# pico_v2.net
KiCad netlist of a schematic drawn in EAGLE
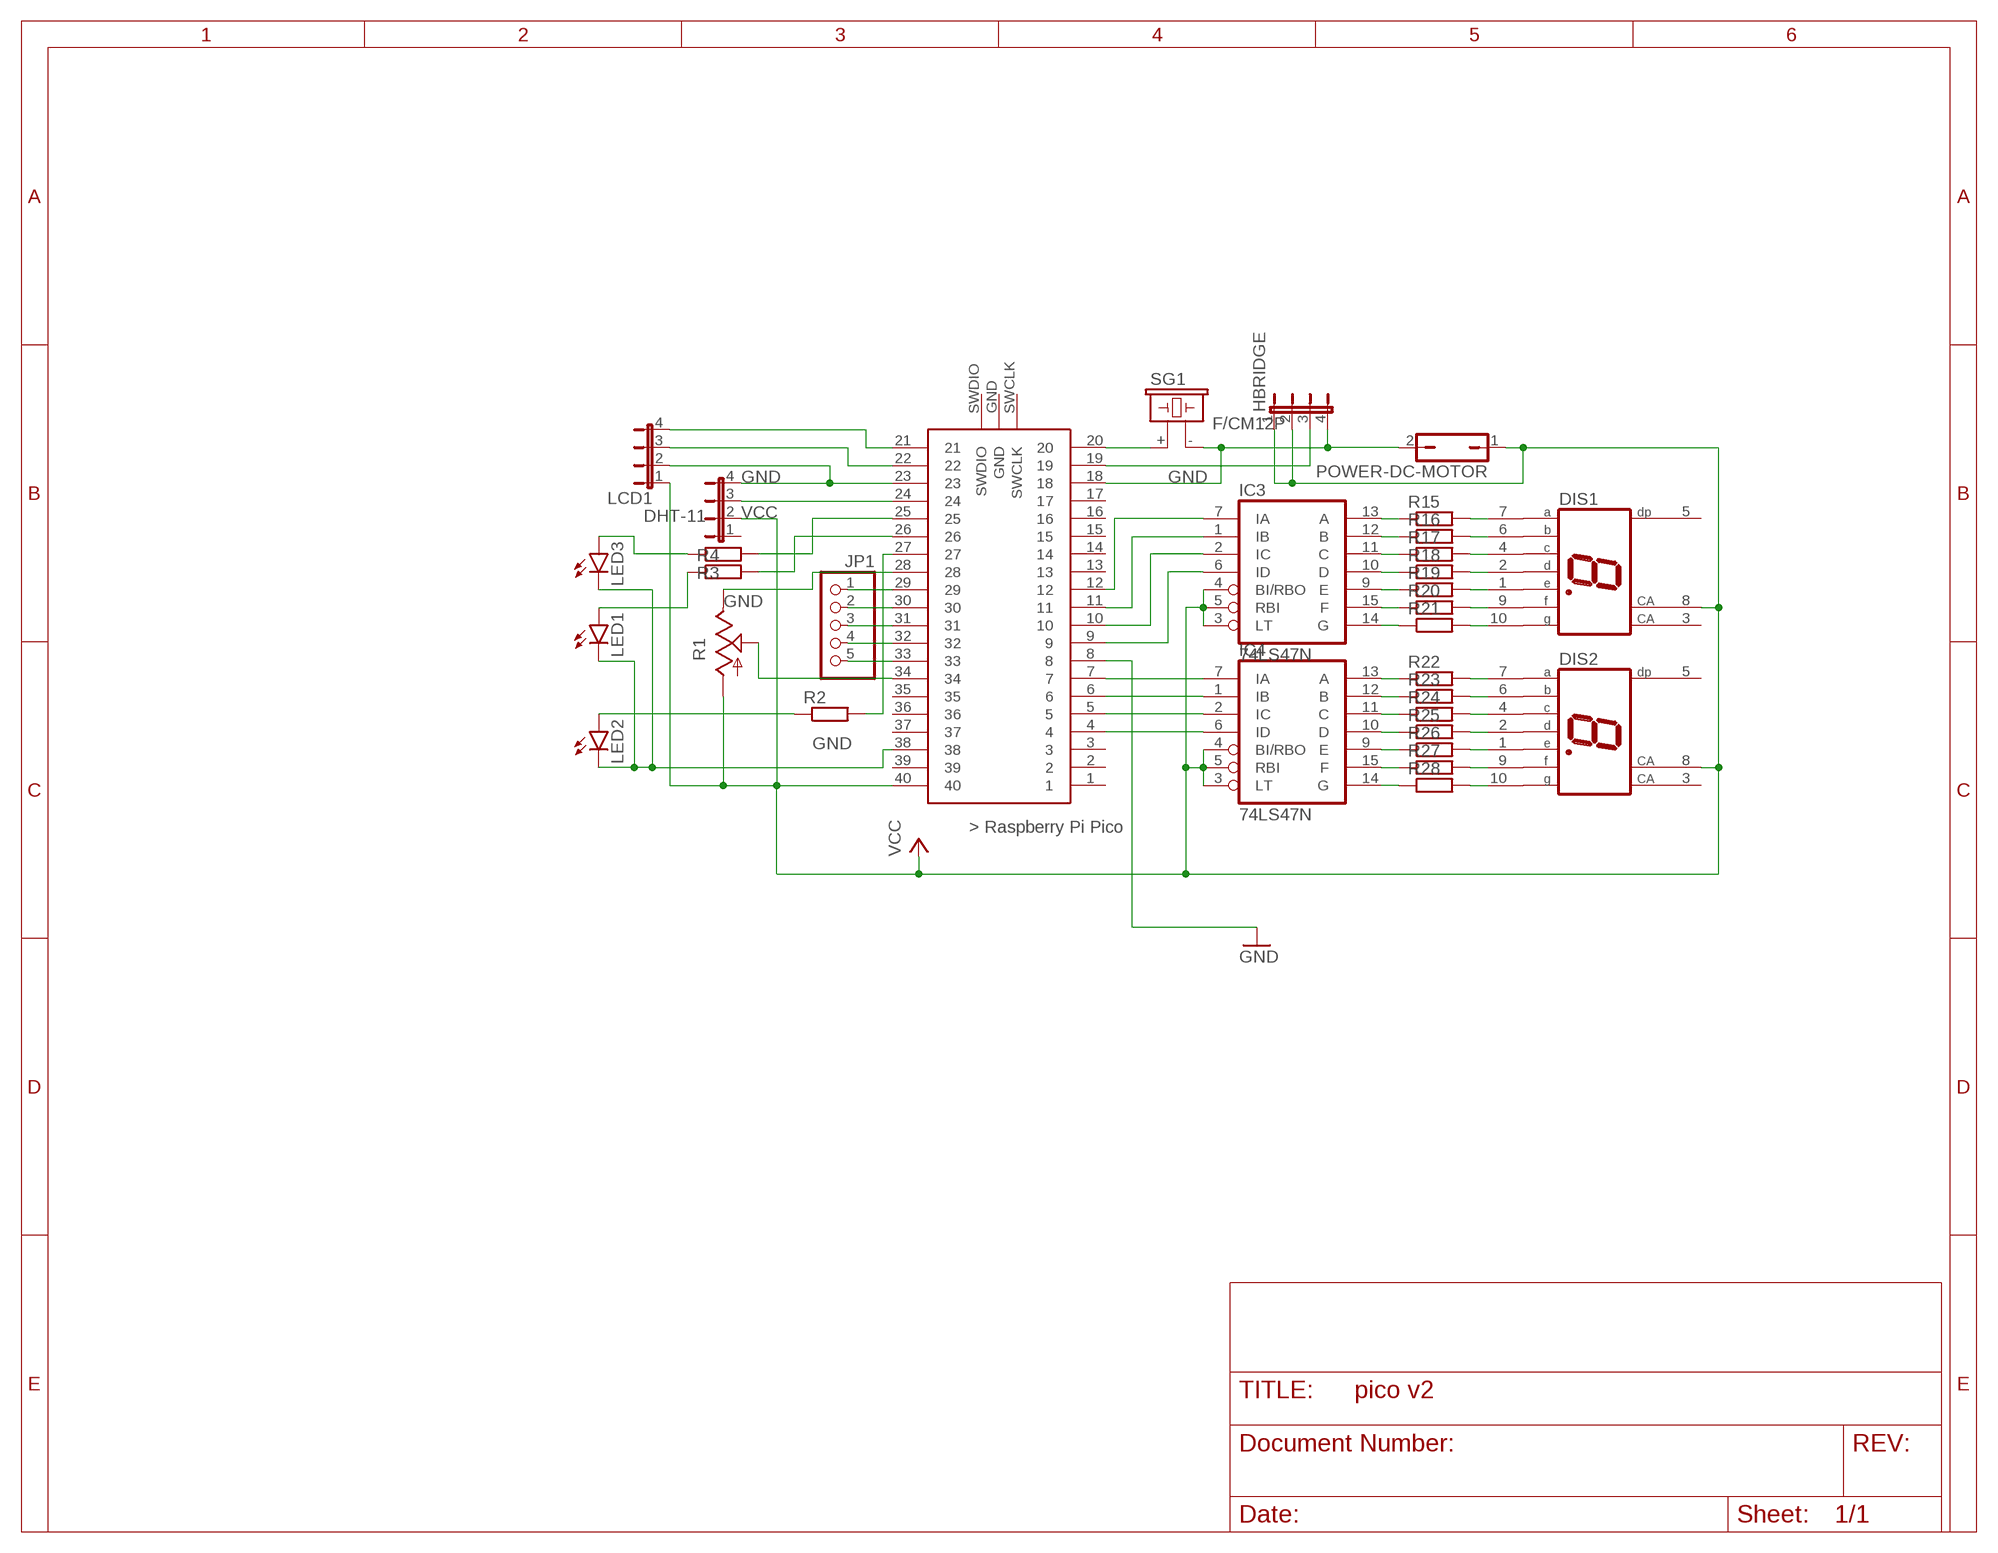
[diagram p0: schematic, sheet 1]

(export (version "E")
  (design (tool "Eeschema 10.0.6"))
  (components
    (comp (ref "DHT-11")
      (value "JP4E")
      (footprint "eagle-import:JP4")
      (libsource (lib "eagle-import") (part "JP4E"))
    )
    (comp (ref "DIS1")
      (value "HD-H101")
      (footprint "eagle-import:HDSP-M")
      (libsource (lib "eagle-import") (part "HD-H101"))
    )
    (comp (ref "DIS2")
      (value "HD-H101")
      (footprint "eagle-import:HDSP-M")
      (libsource (lib "eagle-import") (part "HD-H101"))
    )
    (comp (ref "HBRIDGE")
      (value "JP4E")
      (footprint "eagle-import:JP4")
      (libsource (lib "eagle-import") (part "JP4E"))
    )
    (comp (ref "IC3")
      (value "74LS47N")
      (footprint "eagle-import:DIL16")
      (libsource (lib "eagle-import") (part "7447NLS"))
    )
    (comp (ref "IC4")
      (value "74LS47N")
      (footprint "eagle-import:DIL16")
      (libsource (lib "eagle-import") (part "7447NLS"))
    )
    (comp (ref "JP1")
      (value "PINHD-1X5")
      (footprint "eagle-import:1X05")
      (libsource (lib "eagle-import") (part "PINHD-1X5"))
    )
    (comp (ref "LCD1")
      (value "JP4E")
      (footprint "eagle-import:JP4")
      (libsource (lib "eagle-import") (part "JP4E"))
    )
    (comp (ref "LED1")
      (value "LED5MM")
      (footprint "eagle-import:LED5MM")
      (libsource (lib "eagle-import") (part "LED5MM"))
    )
    (comp (ref "LED2")
      (value "LED5MM")
      (footprint "eagle-import:LED5MM")
      (libsource (lib "eagle-import") (part "LED5MM"))
    )
    (comp (ref "LED3")
      (value "LED5MM")
      (footprint "eagle-import:LED5MM")
      (libsource (lib "eagle-import") (part "LED5MM"))
    )
    (comp (ref "POWER-DC-MOTOR")
      (value "JP1Q")
      (footprint "eagle-import:JP1")
      (libsource (lib "eagle-import") (part "JP1Q"))
    )
    (comp (ref "R1")
      (value "TRIM_US-CA6V")
      (footprint "eagle-import:CA6V")
      (libsource (lib "eagle-import") (part "TRIM_US-CA6V"))
    )
    (comp (ref "R2")
      (value "R-EU_0207/10")
      (footprint "eagle-import:0207_10")
      (libsource (lib "eagle-import") (part "R-EU_0207/10"))
    )
    (comp (ref "R3")
      (value "R-EU_0207/10")
      (footprint "eagle-import:0207_10")
      (libsource (lib "eagle-import") (part "R-EU_0207/10"))
    )
    (comp (ref "R4")
      (value "R-EU_0207/10")
      (footprint "eagle-import:0207_10")
      (libsource (lib "eagle-import") (part "R-EU_0207/10"))
    )
    (comp (ref "R15")
      (value "R-EU_0207/12")
      (footprint "eagle-import:0207_12")
      (libsource (lib "eagle-import") (part "R-EU_0207/12"))
    )
    (comp (ref "R16")
      (value "R-EU_0207/12")
      (footprint "eagle-import:0207_12")
      (libsource (lib "eagle-import") (part "R-EU_0207/12"))
    )
    (comp (ref "R17")
      (value "R-EU_0207/12")
      (footprint "eagle-import:0207_12")
      (libsource (lib "eagle-import") (part "R-EU_0207/12"))
    )
    (comp (ref "R18")
      (value "R-EU_0207/12")
      (footprint "eagle-import:0207_12")
      (libsource (lib "eagle-import") (part "R-EU_0207/12"))
    )
    (comp (ref "R19")
      (value "R-EU_0207/12")
      (footprint "eagle-import:0207_12")
      (libsource (lib "eagle-import") (part "R-EU_0207/12"))
    )
    (comp (ref "R20")
      (value "R-EU_0207/12")
      (footprint "eagle-import:0207_12")
      (libsource (lib "eagle-import") (part "R-EU_0207/12"))
    )
    (comp (ref "R21")
      (value "R-EU_0207/12")
      (footprint "eagle-import:0207_12")
      (libsource (lib "eagle-import") (part "R-EU_0207/12"))
    )
    (comp (ref "R22")
      (value "R-EU_0207/12")
      (footprint "eagle-import:0207_12")
      (libsource (lib "eagle-import") (part "R-EU_0207/12"))
    )
    (comp (ref "R23")
      (value "R-EU_0207/12")
      (footprint "eagle-import:0207_12")
      (libsource (lib "eagle-import") (part "R-EU_0207/12"))
    )
    (comp (ref "R24")
      (value "R-EU_0207/12")
      (footprint "eagle-import:0207_12")
      (libsource (lib "eagle-import") (part "R-EU_0207/12"))
    )
    (comp (ref "R25")
      (value "R-EU_0207/12")
      (footprint "eagle-import:0207_12")
      (libsource (lib "eagle-import") (part "R-EU_0207/12"))
    )
    (comp (ref "R26")
      (value "R-EU_0207/12")
      (footprint "eagle-import:0207_12")
      (libsource (lib "eagle-import") (part "R-EU_0207/12"))
    )
    (comp (ref "R27")
      (value "R-EU_0207/12")
      (footprint "eagle-import:0207_12")
      (libsource (lib "eagle-import") (part "R-EU_0207/12"))
    )
    (comp (ref "R28")
      (value "R-EU_0207/12")
      (footprint "eagle-import:0207_12")
      (libsource (lib "eagle-import") (part "R-EU_0207/12"))
    )
    (comp (ref "SG1")
      (value "F/CM12P")
      (footprint "eagle-import:F_CM12P")
      (libsource (lib "eagle-import") (part "F/CM12P"))
    )
    (comp (ref "U$1")
      (value "RASPBERRY-PI-PICO_TH")
      (footprint "eagle-import:FT_RASPBERRY-PI-PICO_TH")
      (libsource (lib "eagle-import") (part "RASPBERRY-PI-PICO_TH"))
    )
  )
  (nets
    (net (code "1") (name "GND") (class "Default")
      (node (ref "DHT-11") (pin "4") (pinfunction "4_4") (pintype "passive"))
      (node (ref "HBRIDGE") (pin "4") (pinfunction "4_4") (pintype "passive"))
      (node (ref "LCD1") (pin "2") (pinfunction "2_2") (pintype "passive"))
      (node (ref "LED1") (pin "K") (pinfunction "C_K") (pintype "passive"))
      (node (ref "LED2") (pin "K") (pinfunction "C_K") (pintype "passive"))
      (node (ref "LED3") (pin "K") (pinfunction "C_K") (pintype "passive"))
      (node (ref "POWER-DC-MOTOR") (pin "2") (pinfunction "2_2") (pintype "passive"))
      (node (ref "R1") (pin "E") (pinfunction "E_E") (pintype "passive"))
      (node (ref "SG1") (pin "-") (pinfunction "2_-") (pintype "passive"))
      (node (ref "U$1") (pin "18") (pinfunction "18_18") (pintype "bidirectional"))
      (node (ref "U$1") (pin "23") (pinfunction "23_23") (pintype "bidirectional"))
      (node (ref "U$1") (pin "28") (pinfunction "28_28") (pintype "bidirectional"))
      (node (ref "U$1") (pin "38") (pinfunction "38_38") (pintype "bidirectional"))
      (node (ref "U$1") (pin "8") (pinfunction "8_8") (pintype "bidirectional"))
    )
    (net (code "2") (name "Net-(DHT-11-Pad3)") (class "Default")
      (node (ref "DHT-11") (pin "3") (pinfunction "3_3") (pintype "passive"))
      (node (ref "U$1") (pin "24") (pinfunction "24_24") (pintype "bidirectional"))
    )
    (net (code "3") (name "Net-(DIS1-A)") (class "Default")
      (node (ref "DIS1") (pin "7") (pinfunction "A_7") (pintype "passive"))
      (node (ref "R15") (pin "2") (pinfunction "2_2") (pintype "passive"))
    )
    (net (code "4") (name "Net-(DIS1-B)") (class "Default")
      (node (ref "DIS1") (pin "6") (pinfunction "B_6") (pintype "passive"))
      (node (ref "R16") (pin "2") (pinfunction "2_2") (pintype "passive"))
    )
    (net (code "5") (name "Net-(DIS1-C)") (class "Default")
      (node (ref "DIS1") (pin "4") (pinfunction "C_4") (pintype "passive"))
      (node (ref "R17") (pin "2") (pinfunction "2_2") (pintype "passive"))
    )
    (net (code "6") (name "Net-(DIS1-D)") (class "Default")
      (node (ref "DIS1") (pin "2") (pinfunction "D_2") (pintype "passive"))
      (node (ref "R18") (pin "2") (pinfunction "2_2") (pintype "passive"))
    )
    (net (code "7") (name "Net-(DIS1-E)") (class "Default")
      (node (ref "DIS1") (pin "1") (pinfunction "E_1") (pintype "passive"))
      (node (ref "R19") (pin "2") (pinfunction "2_2") (pintype "passive"))
    )
    (net (code "8") (name "Net-(DIS1-F)") (class "Default")
      (node (ref "DIS1") (pin "9") (pinfunction "F_9") (pintype "passive"))
      (node (ref "R20") (pin "2") (pinfunction "2_2") (pintype "passive"))
    )
    (net (code "9") (name "Net-(DIS1-G)") (class "Default")
      (node (ref "DIS1") (pin "10") (pinfunction "G_10") (pintype "passive"))
      (node (ref "R21") (pin "2") (pinfunction "2_2") (pintype "passive"))
    )
    (net (code "10") (name "Net-(DIS2-A)") (class "Default")
      (node (ref "DIS2") (pin "7") (pinfunction "A_7") (pintype "passive"))
      (node (ref "R22") (pin "2") (pinfunction "2_2") (pintype "passive"))
    )
    (net (code "11") (name "Net-(DIS2-B)") (class "Default")
      (node (ref "DIS2") (pin "6") (pinfunction "B_6") (pintype "passive"))
      (node (ref "R23") (pin "2") (pinfunction "2_2") (pintype "passive"))
    )
    (net (code "12") (name "Net-(DIS2-C)") (class "Default")
      (node (ref "DIS2") (pin "4") (pinfunction "C_4") (pintype "passive"))
      (node (ref "R24") (pin "2") (pinfunction "2_2") (pintype "passive"))
    )
    (net (code "13") (name "Net-(DIS2-D)") (class "Default")
      (node (ref "DIS2") (pin "2") (pinfunction "D_2") (pintype "passive"))
      (node (ref "R25") (pin "2") (pinfunction "2_2") (pintype "passive"))
    )
    (net (code "14") (name "Net-(DIS2-E)") (class "Default")
      (node (ref "DIS2") (pin "1") (pinfunction "E_1") (pintype "passive"))
      (node (ref "R26") (pin "2") (pinfunction "2_2") (pintype "passive"))
    )
    (net (code "15") (name "Net-(DIS2-F)") (class "Default")
      (node (ref "DIS2") (pin "9") (pinfunction "F_9") (pintype "passive"))
      (node (ref "R27") (pin "2") (pinfunction "2_2") (pintype "passive"))
    )
    (net (code "16") (name "Net-(DIS2-G)") (class "Default")
      (node (ref "DIS2") (pin "10") (pinfunction "G_10") (pintype "passive"))
      (node (ref "R28") (pin "2") (pinfunction "2_2") (pintype "passive"))
    )
    (net (code "17") (name "Net-(HBRIDGE-Pad3)") (class "Default")
      (node (ref "HBRIDGE") (pin "3") (pinfunction "3_3") (pintype "passive"))
      (node (ref "U$1") (pin "19") (pinfunction "19_19") (pintype "bidirectional"))
    )
    (net (code "18") (name "Net-(IC3A-A)") (class "Default")
      (node (ref "IC3") (pin "13") (pinfunction "A_13") (pintype "output"))
      (node (ref "R15") (pin "1") (pinfunction "1_1") (pintype "passive"))
    )
    (net (code "19") (name "Net-(IC3A-B)") (class "Default")
      (node (ref "IC3") (pin "12") (pinfunction "B_12") (pintype "output"))
      (node (ref "R16") (pin "1") (pinfunction "1_1") (pintype "passive"))
    )
    (net (code "20") (name "Net-(IC3A-C)") (class "Default")
      (node (ref "IC3") (pin "11") (pinfunction "C_11") (pintype "output"))
      (node (ref "R17") (pin "1") (pinfunction "1_1") (pintype "passive"))
    )
    (net (code "21") (name "Net-(IC3A-D)") (class "Default")
      (node (ref "IC3") (pin "10") (pinfunction "D_10") (pintype "output"))
      (node (ref "R18") (pin "1") (pinfunction "1_1") (pintype "passive"))
    )
    (net (code "22") (name "Net-(IC3A-E)") (class "Default")
      (node (ref "IC3") (pin "9") (pinfunction "E_9") (pintype "output"))
      (node (ref "R19") (pin "1") (pinfunction "1_1") (pintype "passive"))
    )
    (net (code "23") (name "Net-(IC3A-F)") (class "Default")
      (node (ref "IC3") (pin "15") (pinfunction "F_15") (pintype "output"))
      (node (ref "R20") (pin "1") (pinfunction "1_1") (pintype "passive"))
    )
    (net (code "24") (name "Net-(IC3A-G)") (class "Default")
      (node (ref "IC3") (pin "14") (pinfunction "G_14") (pintype "output"))
      (node (ref "R21") (pin "1") (pinfunction "1_1") (pintype "passive"))
    )
    (net (code "25") (name "Net-(IC3A-IA)") (class "Default")
      (node (ref "IC3") (pin "7") (pinfunction "IA_7") (pintype "input"))
      (node (ref "U$1") (pin "12") (pinfunction "12_12") (pintype "bidirectional"))
    )
    (net (code "26") (name "Net-(IC3A-IB)") (class "Default")
      (node (ref "IC3") (pin "1") (pinfunction "IB_1") (pintype "input"))
      (node (ref "U$1") (pin "11") (pinfunction "11_11") (pintype "bidirectional"))
    )
    (net (code "27") (name "Net-(IC3A-IC)") (class "Default")
      (node (ref "IC3") (pin "2") (pinfunction "IC_2") (pintype "input"))
      (node (ref "U$1") (pin "10") (pinfunction "10_10") (pintype "bidirectional"))
    )
    (net (code "28") (name "Net-(IC3A-ID)") (class "Default")
      (node (ref "IC3") (pin "6") (pinfunction "ID_6") (pintype "input"))
      (node (ref "U$1") (pin "9") (pinfunction "9_9") (pintype "bidirectional"))
    )
    (net (code "29") (name "Net-(IC4A-A)") (class "Default")
      (node (ref "IC4") (pin "13") (pinfunction "A_13") (pintype "output"))
      (node (ref "R22") (pin "1") (pinfunction "1_1") (pintype "passive"))
    )
    (net (code "30") (name "Net-(IC4A-B)") (class "Default")
      (node (ref "IC4") (pin "12") (pinfunction "B_12") (pintype "output"))
      (node (ref "R23") (pin "1") (pinfunction "1_1") (pintype "passive"))
    )
    (net (code "31") (name "Net-(IC4A-C)") (class "Default")
      (node (ref "IC4") (pin "11") (pinfunction "C_11") (pintype "output"))
      (node (ref "R24") (pin "1") (pinfunction "1_1") (pintype "passive"))
    )
    (net (code "32") (name "Net-(IC4A-D)") (class "Default")
      (node (ref "IC4") (pin "10") (pinfunction "D_10") (pintype "output"))
      (node (ref "R25") (pin "1") (pinfunction "1_1") (pintype "passive"))
    )
    (net (code "33") (name "Net-(IC4A-E)") (class "Default")
      (node (ref "IC4") (pin "9") (pinfunction "E_9") (pintype "output"))
      (node (ref "R26") (pin "1") (pinfunction "1_1") (pintype "passive"))
    )
    (net (code "34") (name "Net-(IC4A-F)") (class "Default")
      (node (ref "IC4") (pin "15") (pinfunction "F_15") (pintype "output"))
      (node (ref "R27") (pin "1") (pinfunction "1_1") (pintype "passive"))
    )
    (net (code "35") (name "Net-(IC4A-G)") (class "Default")
      (node (ref "IC4") (pin "14") (pinfunction "G_14") (pintype "output"))
      (node (ref "R28") (pin "1") (pinfunction "1_1") (pintype "passive"))
    )
    (net (code "36") (name "Net-(IC4A-IA)") (class "Default")
      (node (ref "IC4") (pin "7") (pinfunction "IA_7") (pintype "input"))
      (node (ref "U$1") (pin "7") (pinfunction "7_7") (pintype "bidirectional"))
    )
    (net (code "37") (name "Net-(IC4A-IB)") (class "Default")
      (node (ref "IC4") (pin "1") (pinfunction "IB_1") (pintype "input"))
      (node (ref "U$1") (pin "6") (pinfunction "6_6") (pintype "bidirectional"))
    )
    (net (code "38") (name "Net-(IC4A-IC)") (class "Default")
      (node (ref "IC4") (pin "2") (pinfunction "IC_2") (pintype "input"))
      (node (ref "U$1") (pin "5") (pinfunction "5_5") (pintype "bidirectional"))
    )
    (net (code "39") (name "Net-(IC4A-ID)") (class "Default")
      (node (ref "IC4") (pin "6") (pinfunction "ID_6") (pintype "input"))
      (node (ref "U$1") (pin "4") (pinfunction "4_4") (pintype "bidirectional"))
    )
    (net (code "40") (name "Net-(JP1-Pad1)") (class "Default")
      (node (ref "JP1") (pin "1") (pinfunction "1_1") (pintype "passive"))
      (node (ref "U$1") (pin "29") (pinfunction "29_29") (pintype "bidirectional"))
    )
    (net (code "41") (name "Net-(JP1-Pad2)") (class "Default")
      (node (ref "JP1") (pin "2") (pinfunction "2_2") (pintype "passive"))
      (node (ref "U$1") (pin "30") (pinfunction "30_30") (pintype "bidirectional"))
    )
    (net (code "42") (name "Net-(JP1-Pad3)") (class "Default")
      (node (ref "JP1") (pin "3") (pinfunction "3_3") (pintype "passive"))
      (node (ref "U$1") (pin "31") (pinfunction "31_31") (pintype "bidirectional"))
    )
    (net (code "43") (name "Net-(JP1-Pad4)") (class "Default")
      (node (ref "JP1") (pin "4") (pinfunction "4_4") (pintype "passive"))
      (node (ref "U$1") (pin "32") (pinfunction "32_32") (pintype "bidirectional"))
    )
    (net (code "44") (name "Net-(JP1-Pad5)") (class "Default")
      (node (ref "JP1") (pin "5") (pinfunction "5_5") (pintype "passive"))
      (node (ref "U$1") (pin "33") (pinfunction "33_33") (pintype "bidirectional"))
    )
    (net (code "45") (name "Net-(LCD1-Pad3)") (class "Default")
      (node (ref "LCD1") (pin "3") (pinfunction "3_3") (pintype "passive"))
      (node (ref "U$1") (pin "22") (pinfunction "22_22") (pintype "bidirectional"))
    )
    (net (code "46") (name "Net-(LCD1-Pad4)") (class "Default")
      (node (ref "LCD1") (pin "4") (pinfunction "4_4") (pintype "passive"))
      (node (ref "U$1") (pin "21") (pinfunction "21_21") (pintype "bidirectional"))
    )
    (net (code "47") (name "Net-(LED1-PadA)") (class "Default")
      (node (ref "LED1") (pin "A") (pinfunction "A_A") (pintype "passive"))
      (node (ref "R3") (pin "1") (pinfunction "1_1") (pintype "passive"))
    )
    (net (code "48") (name "Net-(LED2-PadA)") (class "Default")
      (node (ref "LED2") (pin "A") (pinfunction "A_A") (pintype "passive"))
      (node (ref "R2") (pin "1") (pinfunction "1_1") (pintype "passive"))
    )
    (net (code "49") (name "Net-(LED3-PadA)") (class "Default")
      (node (ref "LED3") (pin "A") (pinfunction "A_A") (pintype "passive"))
      (node (ref "R4") (pin "1") (pinfunction "1_1") (pintype "passive"))
    )
    (net (code "50") (name "Net-(R1-PadS)") (class "Default")
      (node (ref "R1") (pin "S") (pinfunction "S_S") (pintype "passive"))
      (node (ref "U$1") (pin "34") (pinfunction "34_34") (pintype "bidirectional"))
    )
    (net (code "51") (name "Net-(R2-Pad2)") (class "Default")
      (node (ref "R2") (pin "2") (pinfunction "2_2") (pintype "passive"))
      (node (ref "U$1") (pin "27") (pinfunction "27_27") (pintype "bidirectional"))
    )
    (net (code "52") (name "Net-(R3-Pad2)") (class "Default")
      (node (ref "R3") (pin "2") (pinfunction "2_2") (pintype "passive"))
      (node (ref "U$1") (pin "26") (pinfunction "26_26") (pintype "bidirectional"))
    )
    (net (code "53") (name "Net-(R4-Pad2)") (class "Default")
      (node (ref "R4") (pin "2") (pinfunction "2_2") (pintype "passive"))
      (node (ref "U$1") (pin "25") (pinfunction "25_25") (pintype "bidirectional"))
    )
    (net (code "54") (name "Net-(SG1-1)") (class "Default")
      (node (ref "SG1") (pin "+") (pinfunction "1_+") (pintype "passive"))
      (node (ref "U$1") (pin "20") (pinfunction "20_20") (pintype "bidirectional"))
    )
    (net (code "55") (name "VCC") (class "Default")
      (node (ref "DHT-11") (pin "2") (pinfunction "2_2") (pintype "passive"))
      (node (ref "DIS1") (pin "8") (pinfunction "CA_8") (pintype "passive"))
      (node (ref "DIS2") (pin "8") (pinfunction "CA_8") (pintype "passive"))
      (node (ref "HBRIDGE") (pin "1") (pinfunction "1_1") (pintype "passive"))
      (node (ref "HBRIDGE") (pin "2") (pinfunction "2_2") (pintype "passive"))
      (node (ref "IC3") (pin "3") (pinfunction "LT_3") (pintype "input"))
      (node (ref "IC3") (pin "4") (pinfunction "BI/RBO_4") (pintype "input"))
      (node (ref "IC3") (pin "5") (pinfunction "RBI_5") (pintype "input"))
      (node (ref "IC4") (pin "3") (pinfunction "LT_3") (pintype "input"))
      (node (ref "IC4") (pin "4") (pinfunction "BI/RBO_4") (pintype "input"))
      (node (ref "IC4") (pin "5") (pinfunction "RBI_5") (pintype "input"))
      (node (ref "LCD1") (pin "1") (pinfunction "1_1") (pintype "passive"))
      (node (ref "POWER-DC-MOTOR") (pin "1") (pinfunction "1_1") (pintype "passive"))
      (node (ref "R1") (pin "A") (pinfunction "A_A") (pintype "passive"))
      (node (ref "U$1") (pin "40") (pinfunction "40_40") (pintype "bidirectional"))
    )
    (net (code "56") (name "unconnected-(DHT-11-Pad1)") (class "Default")
      (node (ref "DHT-11") (pin "1") (pinfunction "1_1") (pintype "passive"))
    )
    (net (code "57") (name "unconnected-(DIS1-CA-Pad3)") (class "Default")
      (node (ref "DIS1") (pin "3") (pinfunction "CA_3") (pintype "passive"))
    )
    (net (code "58") (name "unconnected-(DIS1-DP-Pad5)") (class "Default")
      (node (ref "DIS1") (pin "5") (pinfunction "DP_5") (pintype "passive"))
    )
    (net (code "59") (name "unconnected-(DIS2-CA-Pad3)") (class "Default")
      (node (ref "DIS2") (pin "3") (pinfunction "CA_3") (pintype "passive"))
    )
    (net (code "60") (name "unconnected-(DIS2-DP-Pad5)") (class "Default")
      (node (ref "DIS2") (pin "5") (pinfunction "DP_5") (pintype "passive"))
    )
    (net (code "61") (name "unconnected-(U$1-Pad1)") (class "Default")
      (node (ref "U$1") (pin "1") (pinfunction "1_1") (pintype "bidirectional"))
    )
    (net (code "62") (name "unconnected-(U$1-Pad2)") (class "Default")
      (node (ref "U$1") (pin "2") (pinfunction "2_2") (pintype "bidirectional"))
    )
    (net (code "63") (name "unconnected-(U$1-Pad3)") (class "Default")
      (node (ref "U$1") (pin "3") (pinfunction "3_3") (pintype "bidirectional"))
    )
    (net (code "64") (name "unconnected-(U$1-Pad13)") (class "Default")
      (node (ref "U$1") (pin "13") (pinfunction "13_13") (pintype "bidirectional"))
    )
    (net (code "65") (name "unconnected-(U$1-Pad14)") (class "Default")
      (node (ref "U$1") (pin "14") (pinfunction "14_14") (pintype "bidirectional"))
    )
    (net (code "66") (name "unconnected-(U$1-Pad15)") (class "Default")
      (node (ref "U$1") (pin "15") (pinfunction "15_15") (pintype "bidirectional"))
    )
    (net (code "67") (name "unconnected-(U$1-Pad16)") (class "Default")
      (node (ref "U$1") (pin "16") (pinfunction "16_16") (pintype "bidirectional"))
    )
    (net (code "68") (name "unconnected-(U$1-Pad17)") (class "Default")
      (node (ref "U$1") (pin "17") (pinfunction "17_17") (pintype "bidirectional"))
    )
    (net (code "69") (name "unconnected-(U$1-Pad35)") (class "Default")
      (node (ref "U$1") (pin "35") (pinfunction "35_35") (pintype "bidirectional"))
    )
    (net (code "70") (name "unconnected-(U$1-Pad36)") (class "Default")
      (node (ref "U$1") (pin "36") (pinfunction "36_36") (pintype "bidirectional"))
    )
    (net (code "71") (name "unconnected-(U$1-Pad37)") (class "Default")
      (node (ref "U$1") (pin "37") (pinfunction "37_37") (pintype "bidirectional"))
    )
    (net (code "72") (name "unconnected-(U$1-Pad39)") (class "Default")
      (node (ref "U$1") (pin "39") (pinfunction "39_39") (pintype "bidirectional"))
    )
    (net (code "73") (name "unconnected-(U$1-PadGND)") (class "Default")
      (node (ref "U$1") (pin "GND") (pinfunction "GND_GND") (pintype "bidirectional"))
    )
    (net (code "74") (name "unconnected-(U$1-PadSWCLK)") (class "Default")
      (node (ref "U$1") (pin "SWCLK") (pinfunction "SWCLK_SWCLK") (pintype "bidirectional"))
    )
    (net (code "75") (name "unconnected-(U$1-PadSWDIO)") (class "Default")
      (node (ref "U$1") (pin "SWDIO") (pinfunction "SWDIO_SWDIO") (pintype "bidirectional"))
    )
  )
)
